# RELAY_SMT_5V_IM03GR.net
KiCad netlist of a schematic drawn in Altium Designer
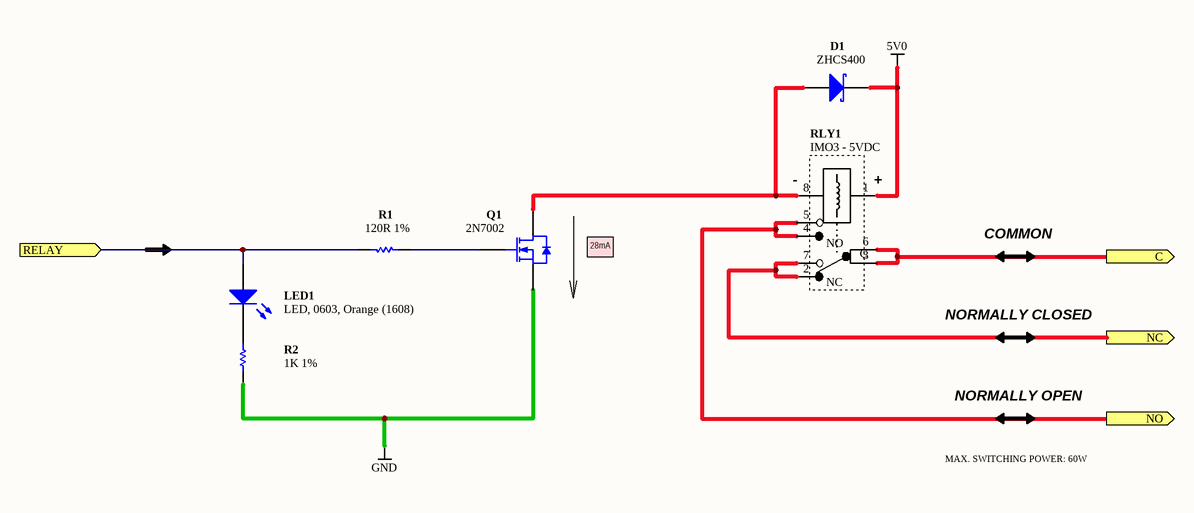
[diagram p0: RELAY_SMT_5V_IM03GR.SchDoc]

(export (version "E")
  (design (tool "Eeschema 10.0.6"))
  (components
    (comp (ref "D1")
      (value "ZHCS400")
      (footprint "SOD323")
      (description "Schottky Diode, 400mA")
      (libsource (lib "AltiumDesignLibrary") (part "DIO-SCHOTTKY-1S"))
    )
    (comp (ref "LED1")
      (value "LED, 0603, Orange (1608)")
      (footprint "0603LED_ORANGE")
      (libsource (lib "AltiumDesignLibrary") (part "DIO-LED-1S"))
    )
    (comp (ref "Q1")
      (value "2N7002")
      (footprint "SOT95P230-3D")
      (description "N-channel Enhancement Mode Field-effect Transistor")
      (libsource (lib "AltiumDesignLibrary") (part "2N7002"))
    )
    (comp (ref "R1")
      (value "120R 1%")
      (footprint "RESC1005-STAR")
      (description "Resistor, 120R 1% 0402 (1005)")
      (fields (field (name "TOLERANCE") "1 %"))
      (libsource (lib "AltiumDesignLibrary") (part "RES"))
    )
    (comp (ref "R2")
      (value "1K 1%")
      (footprint "RESC1005-STAR")
      (description "Resistor, 1K 1% 0402 (1005)")
      (fields (field (name "TOLERANCE") "1 %"))
      (libsource (lib "AltiumDesignLibrary") (part "RES"))
    )
    (comp (ref "RLY1")
      (value "IMO3 - 5VDC")
      (footprint "IM03GR")
      (description "Relay, Tyco IM03GR")
      (libsource (lib "AltiumDesignLibrary") (part "IM03GR"))
    )
  )
  (nets
    (net (code "1") (name "/C") (class "Default")
      (node (ref "RLY1") (pin "3") (pinfunction "3_3") (pintype "passive"))
      (node (ref "RLY1") (pin "6") (pinfunction "6_6") (pintype "passive"))
    )
    (net (code "2") (name "/NC") (class "Default")
      (node (ref "RLY1") (pin "2") (pinfunction "2_2") (pintype "passive"))
      (node (ref "RLY1") (pin "7") (pinfunction "7_7") (pintype "passive"))
    )
    (net (code "3") (name "/NO") (class "Default")
      (node (ref "RLY1") (pin "4") (pinfunction "4_4") (pintype "passive"))
      (node (ref "RLY1") (pin "5") (pinfunction "5_5") (pintype "passive"))
    )
    (net (code "4") (name "/RELAY") (class "Default")
      (node (ref "LED1") (pin "1") (pinfunction "A_1") (pintype "passive"))
      (node (ref "R1") (pin "1") (pinfunction "1_1") (pintype "passive"))
    )
    (net (code "5") (name "5V0") (class "Default")
      (node (ref "D1") (pin "2") (pinfunction "K_2") (pintype "passive"))
      (node (ref "RLY1") (pin "1") (pinfunction "+_1") (pintype "passive"))
    )
    (net (code "6") (name "GND") (class "Default")
      (node (ref "Q1") (pin "3") (pinfunction "S_3") (pintype "passive"))
      (node (ref "R2") (pin "1") (pinfunction "1_1") (pintype "passive"))
    )
    (net (code "7") (name "Net-(D1-A)") (class "Default")
      (node (ref "D1") (pin "1") (pinfunction "A_1") (pintype "passive"))
      (node (ref "Q1") (pin "2") (pinfunction "D_2") (pintype "passive"))
      (node (ref "RLY1") (pin "8") (pinfunction "-_8") (pintype "passive"))
    )
    (net (code "8") (name "Net-(LED1-K)") (class "Default")
      (node (ref "LED1") (pin "2") (pinfunction "K_2") (pintype "passive"))
      (node (ref "R2") (pin "2") (pinfunction "2_2") (pintype "passive"))
    )
    (net (code "9") (name "Net-(Q1-G)") (class "Default")
      (node (ref "Q1") (pin "1") (pinfunction "G_1") (pintype "passive"))
      (node (ref "R1") (pin "2") (pinfunction "2_2") (pintype "passive"))
    )
  )
)
